# Programmateur-ICSP-Atmel.net
KiCad netlist of a schematic drawn in EAGLE
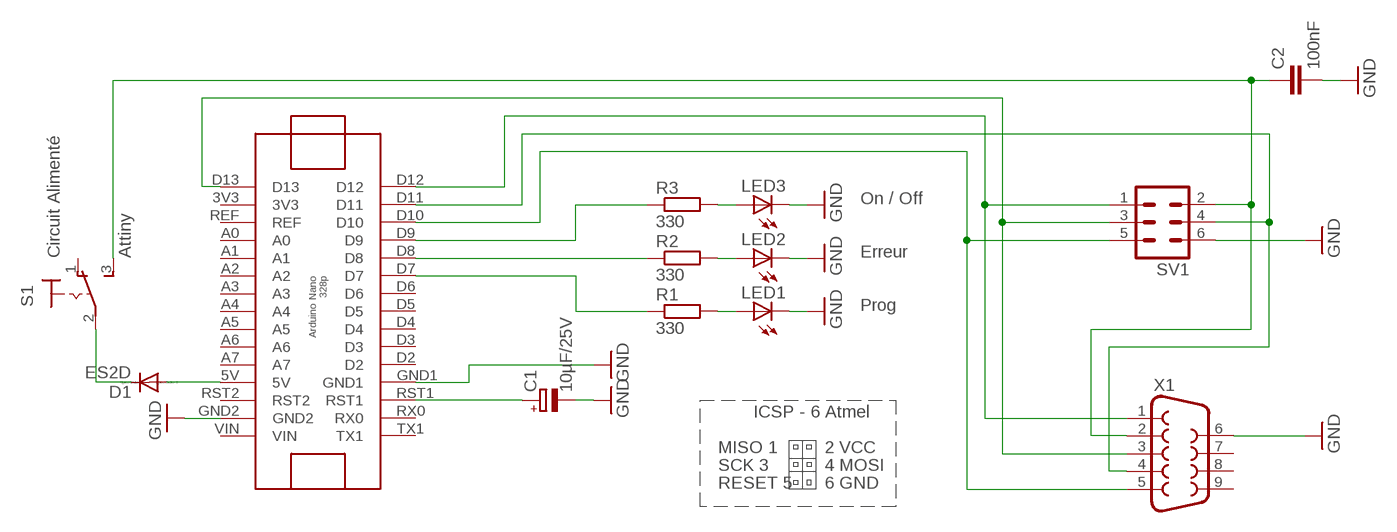
[diagram p0: schematic, sheet 1]

(export (version "E")
  (design (tool "Eeschema 10.0.6"))
  (components
    (comp (ref "ARDUINO-NANO1")
      (value "ARDUINO-NANO")
      (footprint "eagle-import:ARDUINO-NANO")
      (libsource (lib "eagle-import") (part "ARDUINO-NANO"))
    )
    (comp (ref "C1")
      (value "10µF/25V")
      (footprint "eagle-import:E2,5-5")
      (libsource (lib "eagle-import") (part "CPOL-EUE2.5-5"))
    )
    (comp (ref "C2")
      (value "100nF")
      (footprint "eagle-import:C0805")
      (libsource (lib "eagle-import") (part "C-EUC0805"))
    )
    (comp (ref "D1")
      (value "ES2D")
      (footprint "eagle-import:SMB")
      (libsource (lib "eagle-import") (part "ES2D"))
    )
    (comp (ref "LED1")
      (value "LED5MM")
      (footprint "eagle-import:LED5MM")
      (libsource (lib "eagle-import") (part "LED5MM"))
    )
    (comp (ref "LED2")
      (value "LED5MM")
      (footprint "eagle-import:LED5MM")
      (libsource (lib "eagle-import") (part "LED5MM"))
    )
    (comp (ref "LED3")
      (value "LED5MM")
      (footprint "eagle-import:LED5MM")
      (libsource (lib "eagle-import") (part "LED5MM"))
    )
    (comp (ref "R1")
      (value "330")
      (footprint "eagle-import:R0805")
      (libsource (lib "eagle-import") (part "R-EU_R0805"))
    )
    (comp (ref "R2")
      (value "330")
      (footprint "eagle-import:R0805")
      (libsource (lib "eagle-import") (part "R-EU_R0805"))
    )
    (comp (ref "R3")
      (value "330")
      (footprint "eagle-import:R0805")
      (libsource (lib "eagle-import") (part "R-EU_R0805"))
    )
    (comp (ref "S1")
      (value "320-916")
      (footprint "eagle-import:320-916")
      (libsource (lib "eagle-import") (part "320-916"))
    )
    (comp (ref "SV1")
      (value "ML6L")
      (footprint "eagle-import:ML6L")
      (libsource (lib "eagle-import") (part "ML6L"))
    )
    (comp (ref "X1")
      (value "F09HP")
      (footprint "eagle-import:F09HP")
      (libsource (lib "eagle-import") (part "F09HP"))
    )
  )
  (nets
    (net (code "1") (name "GND") (class "Default")
      (node (ref "ARDUINO-NANO1") (pin "GND1") (pinfunction "GND1_GND1") (pintype "input"))
      (node (ref "ARDUINO-NANO1") (pin "GND2") (pinfunction "GND2_GND2") (pintype "bidirectional"))
      (node (ref "C1") (pin "-") (pinfunction "-_-") (pintype "passive"))
      (node (ref "C2") (pin "2") (pinfunction "2_2") (pintype "passive"))
      (node (ref "LED1") (pin "K") (pinfunction "C_K") (pintype "passive"))
      (node (ref "LED2") (pin "K") (pinfunction "C_K") (pintype "passive"))
      (node (ref "LED3") (pin "K") (pinfunction "C_K") (pintype "passive"))
      (node (ref "SV1") (pin "6") (pinfunction "6_6") (pintype "passive"))
      (node (ref "X1") (pin "6") (pinfunction "6_6") (pintype "passive"))
    )
    (net (code "2") (name "Net-(ARDUINO-NANO1-Pad5V)") (class "Default")
      (node (ref "ARDUINO-NANO1") (pin "5V") (pinfunction "5V_5V") (pintype "bidirectional"))
      (node (ref "D1") (pin "A") (pinfunction "A_A") (pintype "passive"))
    )
    (net (code "3") (name "Net-(ARDUINO-NANO1-PadD7)") (class "Default")
      (node (ref "ARDUINO-NANO1") (pin "D7") (pinfunction "D7_D7") (pintype "bidirectional"))
      (node (ref "R1") (pin "1") (pinfunction "1_1") (pintype "passive"))
    )
    (net (code "4") (name "Net-(ARDUINO-NANO1-PadD8)") (class "Default")
      (node (ref "ARDUINO-NANO1") (pin "D8") (pinfunction "D8_D8") (pintype "bidirectional"))
      (node (ref "R2") (pin "1") (pinfunction "1_1") (pintype "passive"))
    )
    (net (code "5") (name "Net-(ARDUINO-NANO1-PadD9)") (class "Default")
      (node (ref "ARDUINO-NANO1") (pin "D9") (pinfunction "D9_D9") (pintype "bidirectional"))
      (node (ref "R3") (pin "1") (pinfunction "1_1") (pintype "passive"))
    )
    (net (code "6") (name "Net-(ARDUINO-NANO1-PadD10)") (class "Default")
      (node (ref "ARDUINO-NANO1") (pin "D10") (pinfunction "D10_D10") (pintype "bidirectional"))
      (node (ref "SV1") (pin "5") (pinfunction "5_5") (pintype "passive"))
      (node (ref "X1") (pin "5") (pinfunction "5_5") (pintype "passive"))
    )
    (net (code "7") (name "Net-(ARDUINO-NANO1-PadD11)") (class "Default")
      (node (ref "ARDUINO-NANO1") (pin "D11") (pinfunction "D11_D11") (pintype "bidirectional"))
      (node (ref "SV1") (pin "4") (pinfunction "4_4") (pintype "passive"))
      (node (ref "X1") (pin "4") (pinfunction "4_4") (pintype "passive"))
    )
    (net (code "8") (name "Net-(ARDUINO-NANO1-PadD12)") (class "Default")
      (node (ref "ARDUINO-NANO1") (pin "D12") (pinfunction "D12_D12") (pintype "bidirectional"))
      (node (ref "SV1") (pin "1") (pinfunction "1_1") (pintype "passive"))
      (node (ref "X1") (pin "1") (pinfunction "1_1") (pintype "passive"))
    )
    (net (code "9") (name "Net-(ARDUINO-NANO1-PadD13)") (class "Default")
      (node (ref "ARDUINO-NANO1") (pin "D13") (pinfunction "D13_D13") (pintype "bidirectional"))
      (node (ref "SV1") (pin "3") (pinfunction "3_3") (pintype "passive"))
      (node (ref "X1") (pin "3") (pinfunction "3_3") (pintype "passive"))
    )
    (net (code "10") (name "Net-(ARDUINO-NANO1-PadRST1)") (class "Default")
      (node (ref "ARDUINO-NANO1") (pin "RST1") (pinfunction "RST1_RST1") (pintype "input"))
      (node (ref "C1") (pin "+") (pinfunction "+_+") (pintype "passive"))
    )
    (net (code "11") (name "Net-(LED1-PadA)") (class "Default")
      (node (ref "LED1") (pin "A") (pinfunction "A_A") (pintype "passive"))
      (node (ref "R1") (pin "2") (pinfunction "2_2") (pintype "passive"))
    )
    (net (code "12") (name "Net-(LED2-PadA)") (class "Default")
      (node (ref "LED2") (pin "A") (pinfunction "A_A") (pintype "passive"))
      (node (ref "R2") (pin "2") (pinfunction "2_2") (pintype "passive"))
    )
    (net (code "13") (name "Net-(LED3-PadA)") (class "Default")
      (node (ref "LED3") (pin "A") (pinfunction "A_A") (pintype "passive"))
      (node (ref "R3") (pin "2") (pinfunction "2_2") (pintype "passive"))
    )
    (net (code "14") (name "Net-(S1-P)") (class "Default")
      (node (ref "D1") (pin "C") (pinfunction "C_C") (pintype "passive"))
      (node (ref "S1") (pin "2") (pinfunction "P_2") (pintype "passive"))
    )
    (net (code "15") (name "Net-(S1-S)") (class "Default")
      (node (ref "C2") (pin "1") (pinfunction "1_1") (pintype "passive"))
      (node (ref "S1") (pin "3") (pinfunction "S_3") (pintype "passive"))
      (node (ref "SV1") (pin "2") (pinfunction "2_2") (pintype "passive"))
      (node (ref "X1") (pin "2") (pinfunction "2_2") (pintype "passive"))
    )
    (net (code "16") (name "unconnected-(ARDUINO-NANO1-Pad3V3)") (class "Default")
      (node (ref "ARDUINO-NANO1") (pin "3V3") (pinfunction "3V3_3V3") (pintype "output"))
    )
    (net (code "17") (name "unconnected-(ARDUINO-NANO1-PadA0)") (class "Default")
      (node (ref "ARDUINO-NANO1") (pin "A0") (pinfunction "A0_A0") (pintype "bidirectional"))
    )
    (net (code "18") (name "unconnected-(ARDUINO-NANO1-PadA1)") (class "Default")
      (node (ref "ARDUINO-NANO1") (pin "A1") (pinfunction "A1_A1") (pintype "bidirectional"))
    )
    (net (code "19") (name "unconnected-(ARDUINO-NANO1-PadA2)") (class "Default")
      (node (ref "ARDUINO-NANO1") (pin "A2") (pinfunction "A2_A2") (pintype "bidirectional"))
    )
    (net (code "20") (name "unconnected-(ARDUINO-NANO1-PadA3)") (class "Default")
      (node (ref "ARDUINO-NANO1") (pin "A3") (pinfunction "A3_A3") (pintype "bidirectional"))
    )
    (net (code "21") (name "unconnected-(ARDUINO-NANO1-PadA4)") (class "Default")
      (node (ref "ARDUINO-NANO1") (pin "A4") (pinfunction "A4_A4") (pintype "bidirectional"))
    )
    (net (code "22") (name "unconnected-(ARDUINO-NANO1-PadA5)") (class "Default")
      (node (ref "ARDUINO-NANO1") (pin "A5") (pinfunction "A5_A5") (pintype "bidirectional"))
    )
    (net (code "23") (name "unconnected-(ARDUINO-NANO1-PadA6)") (class "Default")
      (node (ref "ARDUINO-NANO1") (pin "A6") (pinfunction "A6_A6") (pintype "bidirectional"))
    )
    (net (code "24") (name "unconnected-(ARDUINO-NANO1-PadA7)") (class "Default")
      (node (ref "ARDUINO-NANO1") (pin "A7") (pinfunction "A7_A7") (pintype "output"))
    )
    (net (code "25") (name "unconnected-(ARDUINO-NANO1-PadD2)") (class "Default")
      (node (ref "ARDUINO-NANO1") (pin "D2") (pinfunction "D2_D2") (pintype "bidirectional"))
    )
    (net (code "26") (name "unconnected-(ARDUINO-NANO1-PadD3)") (class "Default")
      (node (ref "ARDUINO-NANO1") (pin "D3") (pinfunction "D3_D3") (pintype "bidirectional"))
    )
    (net (code "27") (name "unconnected-(ARDUINO-NANO1-PadD4)") (class "Default")
      (node (ref "ARDUINO-NANO1") (pin "D4") (pinfunction "D4_D4") (pintype "bidirectional"))
    )
    (net (code "28") (name "unconnected-(ARDUINO-NANO1-PadD5)") (class "Default")
      (node (ref "ARDUINO-NANO1") (pin "D5") (pinfunction "D5_D5") (pintype "bidirectional"))
    )
    (net (code "29") (name "unconnected-(ARDUINO-NANO1-PadD6)") (class "Default")
      (node (ref "ARDUINO-NANO1") (pin "D6") (pinfunction "D6_D6") (pintype "bidirectional"))
    )
    (net (code "30") (name "unconnected-(ARDUINO-NANO1-PadREF)") (class "Default")
      (node (ref "ARDUINO-NANO1") (pin "REF") (pinfunction "REF_REF") (pintype "output"))
    )
    (net (code "31") (name "unconnected-(ARDUINO-NANO1-PadRST2)") (class "Default")
      (node (ref "ARDUINO-NANO1") (pin "RST2") (pinfunction "RST2_RST2") (pintype "bidirectional"))
    )
    (net (code "32") (name "unconnected-(ARDUINO-NANO1-PadRX0)") (class "Default")
      (node (ref "ARDUINO-NANO1") (pin "RX0") (pinfunction "RX0_RX0") (pintype "input"))
    )
    (net (code "33") (name "unconnected-(ARDUINO-NANO1-PadTX1)") (class "Default")
      (node (ref "ARDUINO-NANO1") (pin "TX1") (pinfunction "TX1_TX1") (pintype "output"))
    )
    (net (code "34") (name "unconnected-(ARDUINO-NANO1-PadVIN)") (class "Default")
      (node (ref "ARDUINO-NANO1") (pin "VIN") (pinfunction "VIN_VIN") (pintype "input"))
    )
    (net (code "35") (name "unconnected-(S1-O-Pad1)") (class "Default")
      (node (ref "S1") (pin "1") (pinfunction "O_1") (pintype "passive"))
    )
    (net (code "36") (name "unconnected-(X1-Pad7)") (class "Default")
      (node (ref "X1") (pin "7") (pinfunction "7_7") (pintype "passive"))
    )
    (net (code "37") (name "unconnected-(X1-Pad8)") (class "Default")
      (node (ref "X1") (pin "8") (pinfunction "8_8") (pintype "passive"))
    )
    (net (code "38") (name "unconnected-(X1-Pad9)") (class "Default")
      (node (ref "X1") (pin "9") (pinfunction "9_9") (pintype "passive"))
    )
  )
)
